# Little-Wire_J_N.net
KiCad netlist of a schematic drawn in EAGLE
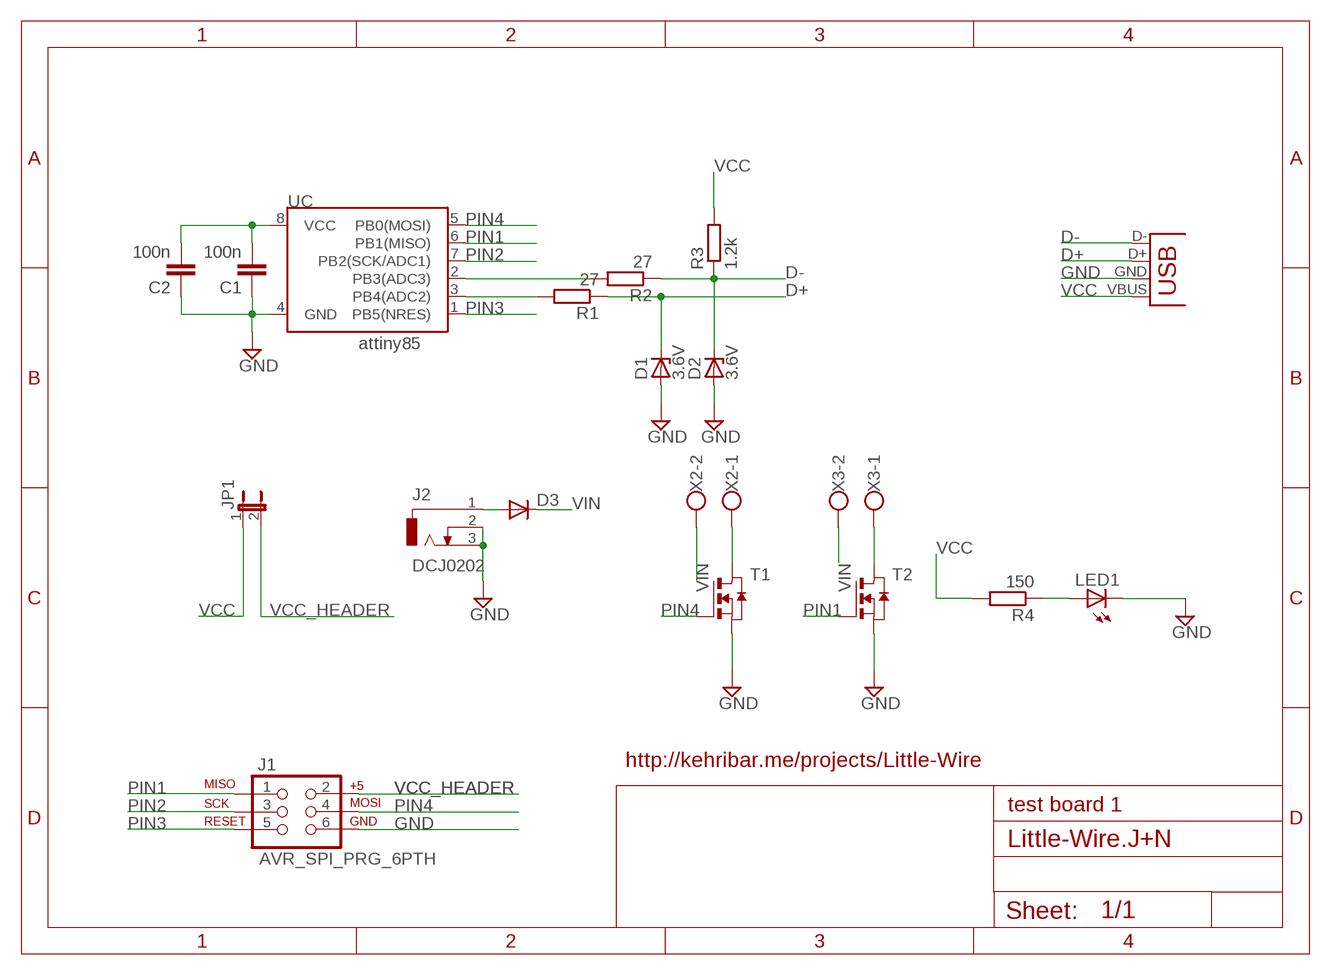
[diagram p0: schematic, sheet 1]

(export (version "E")
  (design (tool "Eeschema 10.0.6"))
  (components
    (comp (ref "C1")
      (value "100n")
      (footprint "eagle-import:C050-025X075")
      (libsource (lib "eagle-import") (part "C-EU050-025X075"))
    )
    (comp (ref "C2")
      (value "100n")
      (footprint "eagle-import:C050-025X075")
      (libsource (lib "eagle-import") (part "C-EU050-025X075"))
    )
    (comp (ref "D1")
      (value "3.6V")
      (footprint "eagle-import:ZDIO-5")
      (libsource (lib "eagle-import") (part "ZENER-DIODEZD-5"))
    )
    (comp (ref "D2")
      (value "3.6V")
      (footprint "eagle-import:ZDIO-5")
      (libsource (lib "eagle-import") (part "ZENER-DIODEZD-5"))
    )
    (comp (ref "D3")
      (value "DIODE-D-7.5")
      (footprint "eagle-import:D-7.5")
      (libsource (lib "eagle-import") (part "DIODE-D-7.5"))
    )
    (comp (ref "J1")
      (value "AVR_SPI_PRG_6PTH")
      (footprint "eagle-import:2X3")
      (libsource (lib "eagle-import") (part "AVR_SPI_PRG_6PTH"))
    )
    (comp (ref "J2")
      (value "DCJ0202")
      (footprint "eagle-import:DCJ0202")
      (libsource (lib "eagle-import") (part "DCJ0202"))
    )
    (comp (ref "JP1")
      (value "JUMPER-2PTH")
      (footprint "eagle-import:1X02")
      (libsource (lib "eagle-import") (part "JUMPER-2PTH"))
    )
    (comp (ref "LED1")
      (value "LED3MM")
      (footprint "eagle-import:LED3MM")
      (libsource (lib "eagle-import") (part "LED3MM"))
    )
    (comp (ref "R1")
      (value "27")
      (footprint "eagle-import:0204_5")
      (libsource (lib "eagle-import") (part "R-EU_0204/5"))
    )
    (comp (ref "R2")
      (value "27")
      (footprint "eagle-import:0204_5")
      (libsource (lib "eagle-import") (part "R-EU_0204/5"))
    )
    (comp (ref "R3")
      (value "1.2k")
      (footprint "eagle-import:0204_5")
      (libsource (lib "eagle-import") (part "R-EU_0204/5"))
    )
    (comp (ref "R4")
      (value "150")
      (footprint "eagle-import:0204_5")
      (libsource (lib "eagle-import") (part "R-EU_0204/5"))
    )
    (comp (ref "T1")
      (value "NMOSSOT223")
      (footprint "eagle-import:SOT223")
      (libsource (lib "eagle-import") (part "NMOSSOT223"))
    )
    (comp (ref "T2")
      (value "NMOSSOT223")
      (footprint "eagle-import:SOT223")
      (libsource (lib "eagle-import") (part "NMOSSOT223"))
    )
    (comp (ref "UC")
      (value "ATTINY45DIP8")
      (footprint "eagle-import:DIP08")
      (libsource (lib "eagle-import") (part "ATTINY45DIP8"))
    )
    (comp (ref "X1")
      (value "USB-A-H")
      (footprint "eagle-import:USB-A-H")
      (libsource (lib "eagle-import") (part "USB-A-H"))
    )
    (comp (ref "X2")
      (value "W237-102")
      (footprint "eagle-import:W237-102")
      (fields (field (name "MPN") "237-102"))
      (libsource (lib "eagle-import") (part "W237-102"))
    )
    (comp (ref "X3")
      (value "W237-102")
      (footprint "eagle-import:W237-102")
      (fields (field (name "MPN") "237-102"))
      (libsource (lib "eagle-import") (part "W237-102"))
    )
  )
  (nets
    (net (code "1") (name "/D+") (class "Default")
      (node (ref "D1") (pin "C") (pinfunction "C_C") (pintype "passive"))
      (node (ref "R1") (pin "1") (pinfunction "1_1") (pintype "passive"))
      (node (ref "X1") (pin "D+") (pinfunction "D-_D+") (pintype "bidirectional"))
    )
    (net (code "2") (name "/D-") (class "Default")
      (node (ref "D2") (pin "C") (pinfunction "C_C") (pintype "passive"))
      (node (ref "R2") (pin "1") (pinfunction "1_1") (pintype "passive"))
      (node (ref "R3") (pin "1") (pinfunction "1_1") (pintype "passive"))
      (node (ref "X1") (pin "D-") (pinfunction "D+_D-") (pintype "bidirectional"))
    )
    (net (code "3") (name "/PIN1") (class "Default")
      (node (ref "J1") (pin "1") (pinfunction "1_1") (pintype "passive"))
      (node (ref "T2") (pin "1") (pinfunction "G_1") (pintype "passive"))
      (node (ref "UC") (pin "6") (pinfunction "PB1(MISO)_6") (pintype "bidirectional"))
    )
    (net (code "4") (name "/PIN2") (class "Default")
      (node (ref "J1") (pin "3") (pinfunction "3_3") (pintype "passive"))
      (node (ref "UC") (pin "7") (pinfunction "PB2(SCK/ADC1)_7") (pintype "bidirectional"))
    )
    (net (code "5") (name "/PIN3") (class "Default")
      (node (ref "J1") (pin "5") (pinfunction "5_5") (pintype "passive"))
      (node (ref "UC") (pin "1") (pinfunction "PB5(NRES)_1") (pintype "bidirectional"))
    )
    (net (code "6") (name "/PIN4") (class "Default")
      (node (ref "J1") (pin "4") (pinfunction "4_4") (pintype "passive"))
      (node (ref "T1") (pin "1") (pinfunction "G_1") (pintype "passive"))
      (node (ref "UC") (pin "5") (pinfunction "PB0(MOSI)_5") (pintype "bidirectional"))
    )
    (net (code "7") (name "/VCC") (class "Default")
      (node (ref "C1") (pin "2") (pinfunction "2_2") (pintype "passive"))
      (node (ref "C2") (pin "2") (pinfunction "2_2") (pintype "passive"))
      (node (ref "JP1") (pin "1") (pinfunction "1_1") (pintype "passive"))
      (node (ref "R3") (pin "2") (pinfunction "2_2") (pintype "passive"))
      (node (ref "R4") (pin "2") (pinfunction "2_2") (pintype "passive"))
      (node (ref "UC") (pin "8") (pinfunction "VCC_8") (pintype "bidirectional"))
      (node (ref "X1") (pin "VBUS") (pinfunction "GND_VBUS") (pintype "bidirectional"))
    )
    (net (code "8") (name "/VCC_HEADER") (class "Default")
      (node (ref "J1") (pin "2") (pinfunction "2_2") (pintype "passive"))
      (node (ref "JP1") (pin "2") (pinfunction "2_2") (pintype "passive"))
    )
    (net (code "9") (name "/VIN") (class "Default")
      (node (ref "D3") (pin "C") (pinfunction "C_C") (pintype "passive"))
      (node (ref "X2") (pin "2") (pinfunction "KL_2") (pintype "passive"))
      (node (ref "X3") (pin "2") (pinfunction "KL_2") (pintype "passive"))
    )
    (net (code "10") (name "GND") (class "Default")
      (node (ref "C1") (pin "1") (pinfunction "1_1") (pintype "passive"))
      (node (ref "C2") (pin "1") (pinfunction "1_1") (pintype "passive"))
      (node (ref "D1") (pin "A") (pinfunction "A_A") (pintype "passive"))
      (node (ref "D2") (pin "A") (pinfunction "A_A") (pintype "passive"))
      (node (ref "J1") (pin "6") (pinfunction "6_6") (pintype "passive"))
      (node (ref "J2") (pin "2") (pinfunction "2_2") (pintype "passive"))
      (node (ref "J2") (pin "3") (pinfunction "3_3") (pintype "passive"))
      (node (ref "LED1") (pin "K") (pinfunction "C_K") (pintype "passive"))
      (node (ref "T1") (pin "3") (pinfunction "S_3") (pintype "passive"))
      (node (ref "T2") (pin "3") (pinfunction "S_3") (pintype "passive"))
      (node (ref "UC") (pin "4") (pinfunction "GND_4") (pintype "bidirectional"))
      (node (ref "X1") (pin "GND") (pinfunction "VBUS_GND") (pintype "bidirectional"))
    )
    (net (code "11") (name "Net-(D3-PadA)") (class "Default")
      (node (ref "D3") (pin "A") (pinfunction "A_A") (pintype "passive"))
      (node (ref "J2") (pin "1") (pinfunction "1_1") (pintype "passive"))
    )
    (net (code "12") (name "Net-(LED1-PadA)") (class "Default")
      (node (ref "LED1") (pin "A") (pinfunction "A_A") (pintype "passive"))
      (node (ref "R4") (pin "1") (pinfunction "1_1") (pintype "passive"))
    )
    (net (code "13") (name "Net-(UC-PB3(ADC3))") (class "Default")
      (node (ref "R2") (pin "2") (pinfunction "2_2") (pintype "passive"))
      (node (ref "UC") (pin "2") (pinfunction "PB3(ADC3)_2") (pintype "bidirectional"))
    )
    (net (code "14") (name "Net-(UC-PB4(ADC2))") (class "Default")
      (node (ref "R1") (pin "2") (pinfunction "2_2") (pintype "passive"))
      (node (ref "UC") (pin "3") (pinfunction "PB4(ADC2)_3") (pintype "bidirectional"))
    )
    (net (code "15") (name "Net-(X2A-KL)") (class "Default")
      (node (ref "T1") (pin "2") (pinfunction "D_2") (pintype "passive"))
      (node (ref "T1") (pin "4") (pinfunction "D_4") (pintype "passive"))
      (node (ref "X2") (pin "1") (pinfunction "KL_1") (pintype "passive"))
    )
    (net (code "16") (name "Net-(X3A-KL)") (class "Default")
      (node (ref "T2") (pin "2") (pinfunction "D_2") (pintype "passive"))
      (node (ref "T2") (pin "4") (pinfunction "D_4") (pintype "passive"))
      (node (ref "X3") (pin "1") (pinfunction "KL_1") (pintype "passive"))
    )
  )
)
